# FRONT-UNIT.net
KiCad netlist of a schematic drawn in Altium Designer
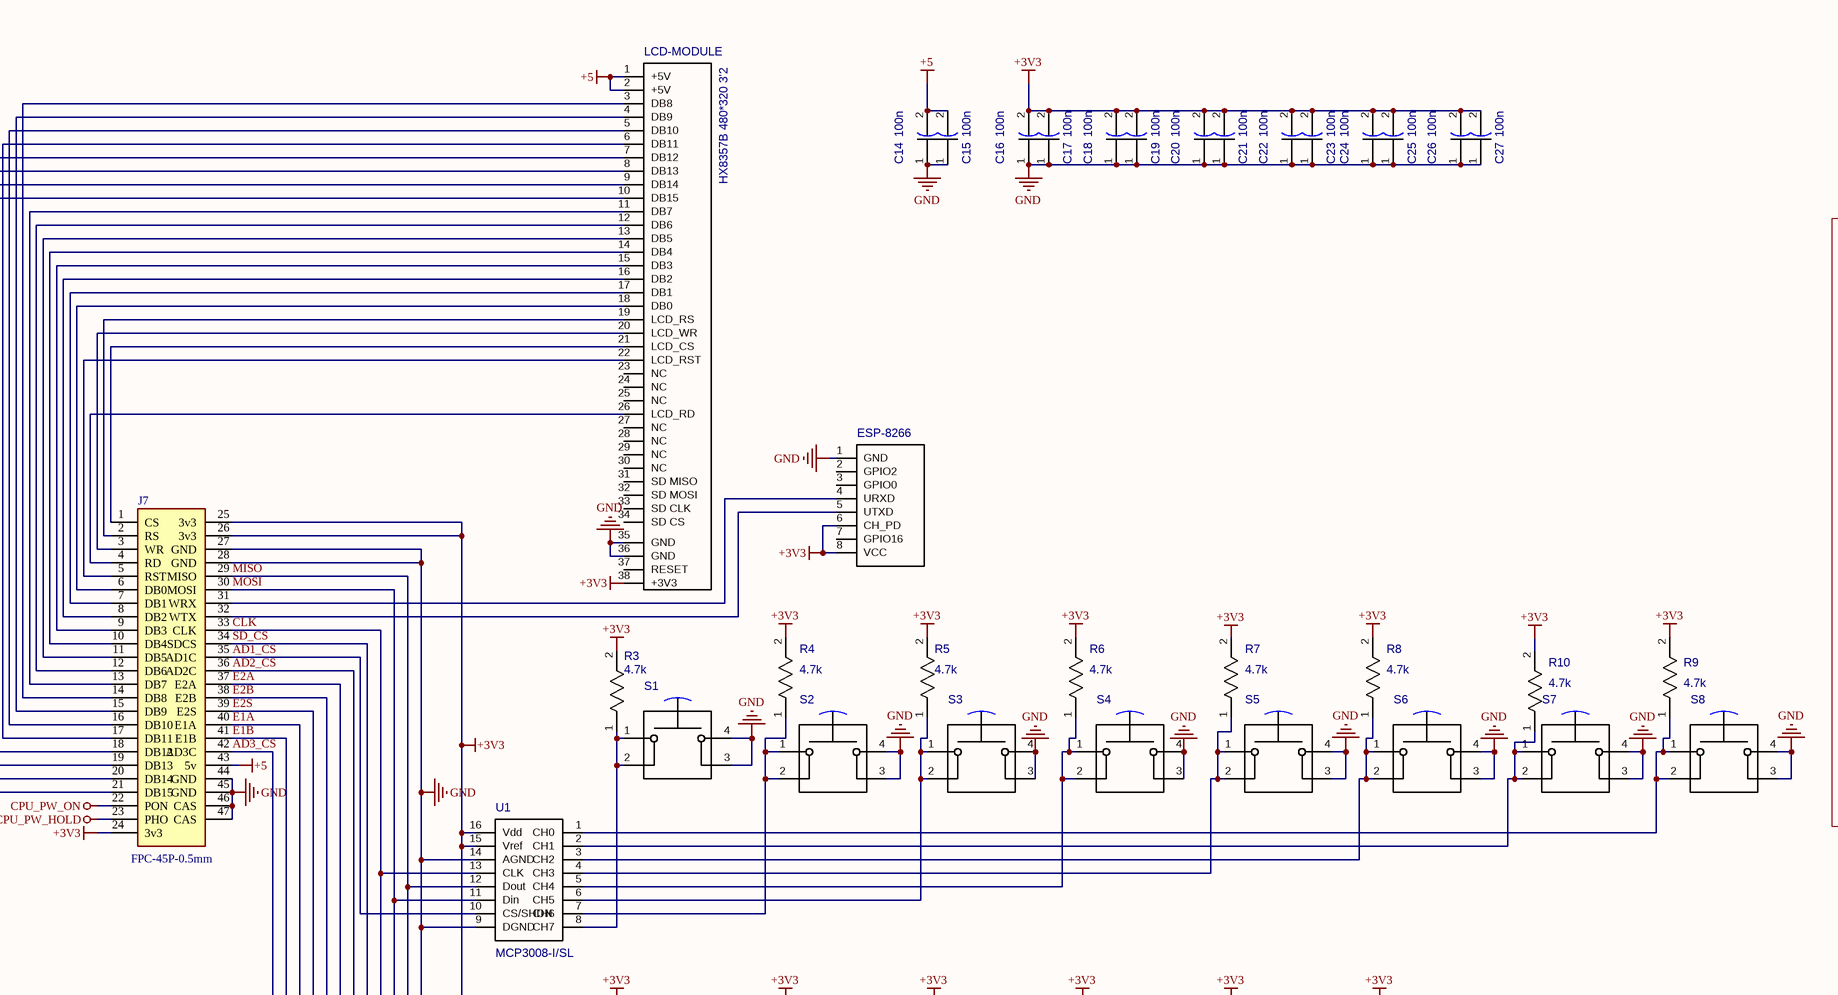
[diagram p0: FRONT-UNIT.SchDoc, top left]
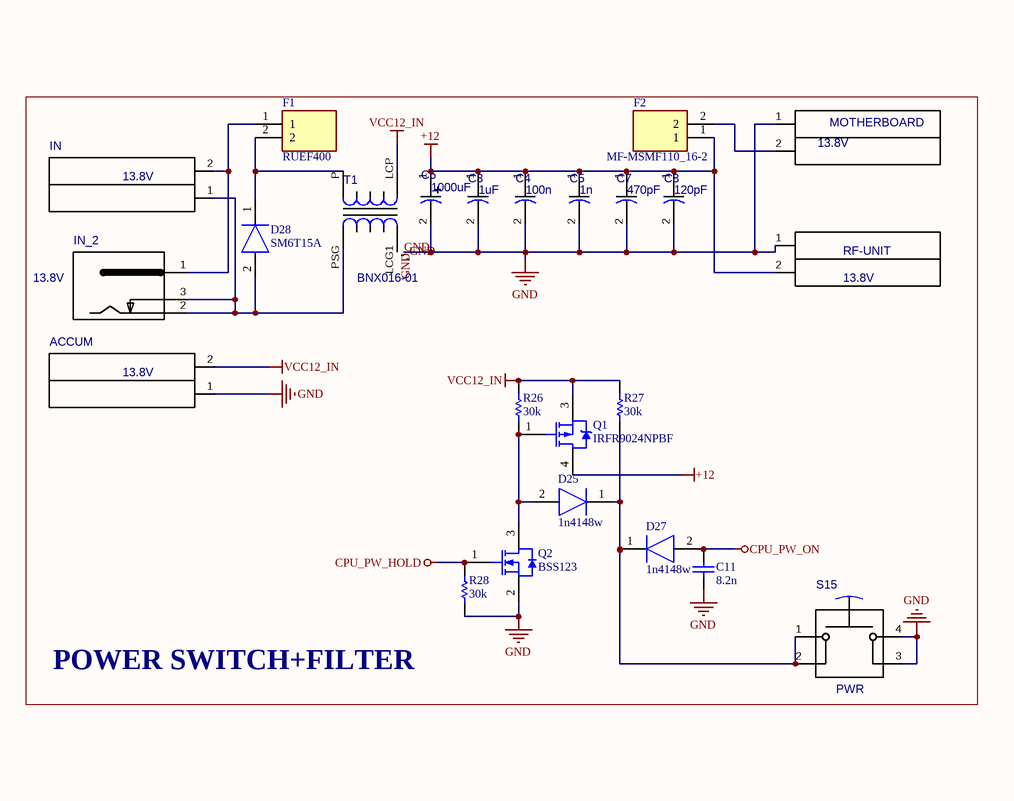
[diagram p1: FRONT-UNIT.SchDoc, top right]
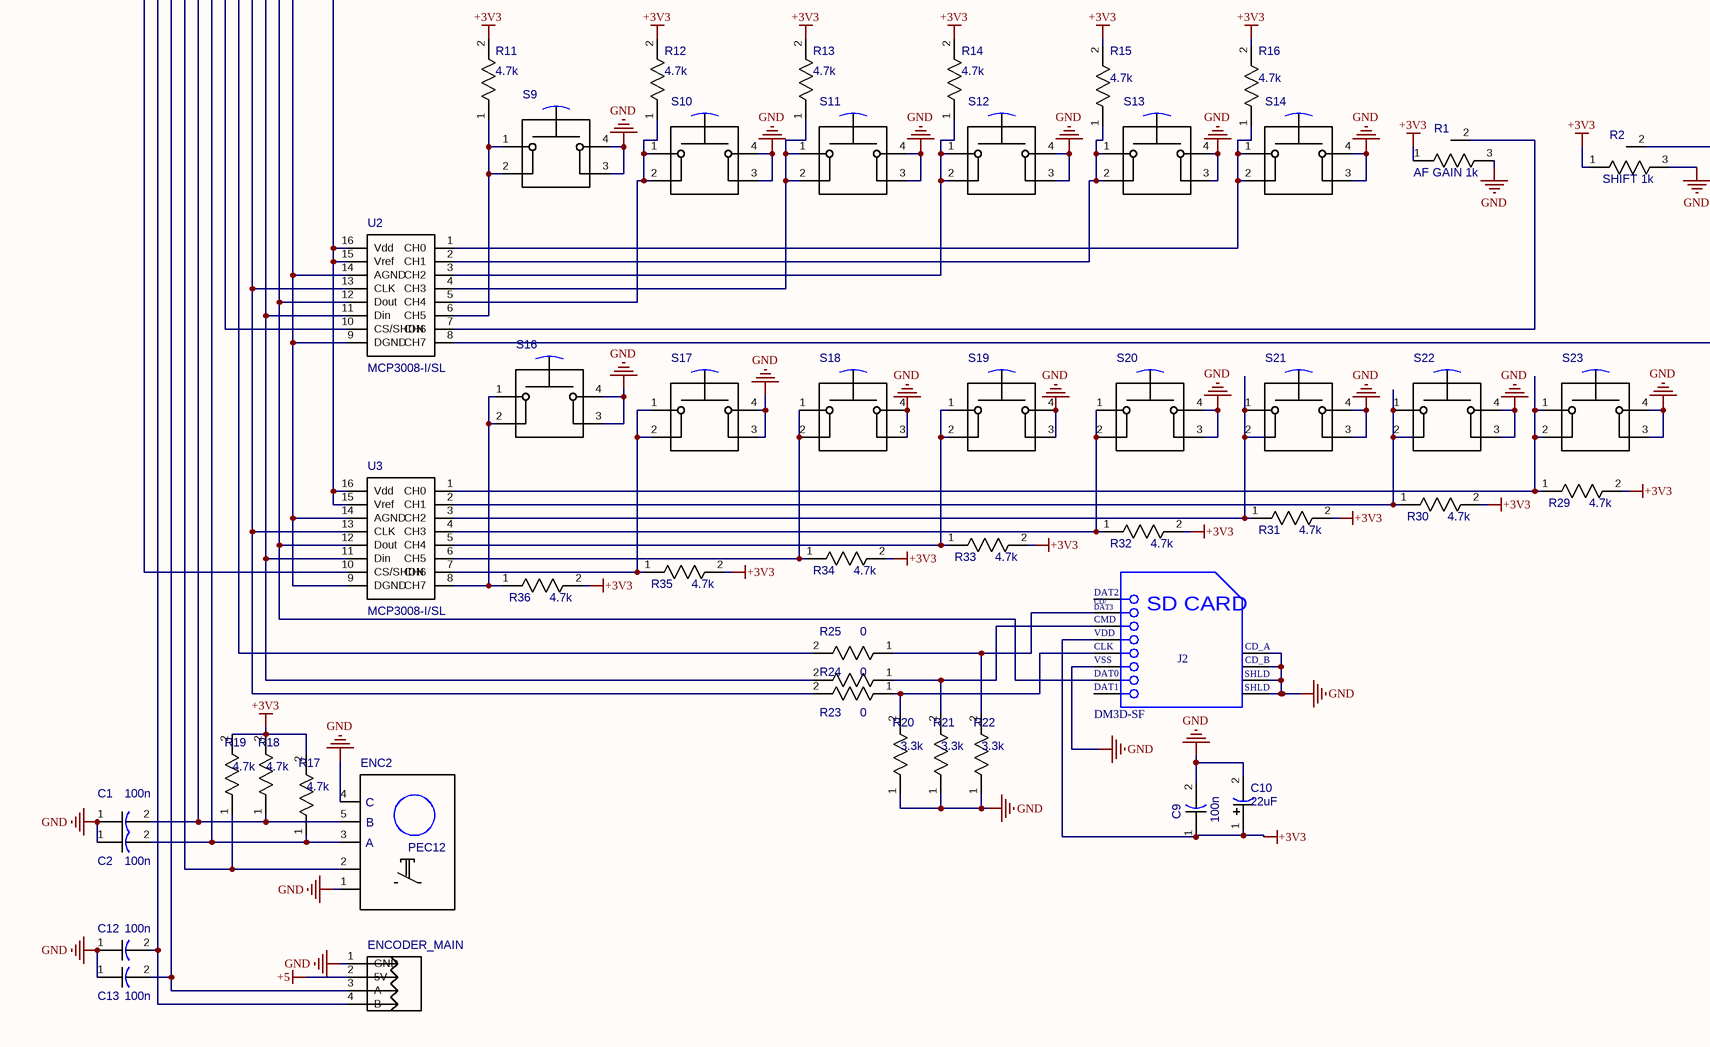
[diagram p2: FRONT-UNIT.SchDoc, bottom left]
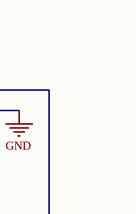
[diagram p3: FRONT-UNIT.SchDoc, bottom right]

(export (version "E")
  (design (tool "Eeschema 10.0.6"))
  (components
    (comp (ref "ACCUM")
      (value "13.8V")
      (footprint "JX2")
      (description "JX2")
      (libsource (lib "*") (part "JX2"))
    )
    (comp (ref "C1")
      (value "100n")
      (footprint "CAP_0805")
      (description "CAP_0805")
      (libsource (lib "*") (part "CAP_0805"))
    )
    (comp (ref "C2")
      (value "100n")
      (footprint "CAP_0805")
      (description "CAP_0805")
      (libsource (lib "*") (part "CAP_0805"))
    )
    (comp (ref "C3")
      (value "1uF")
      (footprint "CAP_1206")
      (description "CAP_1206")
      (libsource (lib "*") (part "CAP_1206"))
    )
    (comp (ref "C4")
      (value "100n")
      (footprint "CAP_1206")
      (description "CAP_1206")
      (libsource (lib "*") (part "CAP_1206"))
    )
    (comp (ref "C5")
      (value "1n")
      (footprint "CAP_1206")
      (description "CAP_1206")
      (libsource (lib "*") (part "CAP_1206"))
    )
    (comp (ref "C6")
      (value "1000uF")
      (footprint "CAP250RP")
      (description "CAP250RP")
      (libsource (lib "*") (part "CAP250RP"))
    )
    (comp (ref "C7")
      (value "470pF")
      (footprint "CAP_1206")
      (description "CAP_1206")
      (libsource (lib "*") (part "CAP_1206"))
    )
    (comp (ref "C8")
      (value "120pF")
      (footprint "CAP_1206")
      (description "CAP_1206")
      (libsource (lib "*") (part "CAP_1206"))
    )
    (comp (ref "C9")
      (value "100n")
      (footprint "CAP_0805")
      (description "CAP_0805")
      (libsource (lib "*") (part "CAP_0805"))
    )
    (comp (ref "C10")
      (value "22uF")
      (footprint "EEEFC_sizeB")
      (description "EEEFC_sizeB")
      (libsource (lib "*") (part "EEEFC_sizeB"))
    )
    (comp (ref "C11")
      (value "8.2n")
      (footprint "CAPC2013X94X50LL20T25")
      (description "CAP_1206")
      (fields
        (field (name "MANUFACTURER") "AVX Interconnect / Elco")
        (field (name "PART NUMBER") "08055C822KAT2A")
      )
      (libsource (lib "Altium Content Vault") (part "CAP"))
    )
    (comp (ref "C12")
      (value "100n")
      (footprint "CAP_0805")
      (description "CAP_0805")
      (libsource (lib "*") (part "CAP_0805"))
    )
    (comp (ref "C13")
      (value "100n")
      (footprint "CAP_0805")
      (description "CAP_0805")
      (libsource (lib "*") (part "CAP_0805"))
    )
    (comp (ref "C14")
      (value "100n")
      (footprint "CAP_0805")
      (description "CAP_0805")
      (libsource (lib "*") (part "CAP_0805"))
    )
    (comp (ref "C15")
      (value "100n")
      (footprint "CAP_0805")
      (description "CAP_0805")
      (libsource (lib "*") (part "CAP_0805"))
    )
    (comp (ref "C16")
      (value "100n")
      (footprint "CAP_0805")
      (description "CAP_0805")
      (libsource (lib "*") (part "CAP_0805"))
    )
    (comp (ref "C17")
      (value "100n")
      (footprint "CAP_0805")
      (description "CAP_0805")
      (libsource (lib "*") (part "CAP_0805"))
    )
    (comp (ref "C18")
      (value "100n")
      (footprint "CAP_0805")
      (description "CAP_0805")
      (libsource (lib "*") (part "CAP_0805"))
    )
    (comp (ref "C19")
      (value "100n")
      (footprint "CAP_0805")
      (description "CAP_0805")
      (libsource (lib "*") (part "CAP_0805"))
    )
    (comp (ref "C20")
      (value "100n")
      (footprint "CAP_0805")
      (description "CAP_0805")
      (libsource (lib "*") (part "CAP_0805"))
    )
    (comp (ref "C21")
      (value "100n")
      (footprint "CAP_0805")
      (description "CAP_0805")
      (libsource (lib "*") (part "CAP_0805"))
    )
    (comp (ref "C22")
      (value "100n")
      (footprint "CAP_0805")
      (description "CAP_0805")
      (libsource (lib "*") (part "CAP_0805"))
    )
    (comp (ref "C23")
      (value "100n")
      (footprint "CAP_0805")
      (description "CAP_0805")
      (libsource (lib "*") (part "CAP_0805"))
    )
    (comp (ref "C24")
      (value "100n")
      (footprint "CAP_0805")
      (description "CAP_0805")
      (libsource (lib "*") (part "CAP_0805"))
    )
    (comp (ref "C25")
      (value "100n")
      (footprint "CAP_0805")
      (description "CAP_0805")
      (libsource (lib "*") (part "CAP_0805"))
    )
    (comp (ref "C26")
      (value "100n")
      (footprint "CAP_0805")
      (description "CAP_0805")
      (libsource (lib "*") (part "CAP_0805"))
    )
    (comp (ref "C27")
      (value "100n")
      (footprint "CAP_0805")
      (description "CAP_0805")
      (libsource (lib "*") (part "CAP_0805"))
    )
    (comp (ref "D25")
      (value "1n4148w")
      (footprint "SamacSys:SOD3716X135N")
      (description "Diode")
      (libsource (lib "*") (part "1n4148w"))
    )
    (comp (ref "D27")
      (value "1n4148w")
      (footprint "SamacSys:SOD3716X135N")
      (description "Diode")
      (libsource (lib "*") (part "1n4148w"))
    )
    (comp (ref "D28")
      (value "SM6T15A")
      (footprint "SamacSys:SMBJ36CATR")
      (description "Diode")
      (fields (field (name "MOUSER PART NUMBER") "511-SM6T15A") (field (name "RS PART NUMBER") "4864915P"))
      (libsource (lib "*") (part "SM6T15A"))
    )
    (comp (ref "ENC2") (value "PEC12") (footprint "PEC12") (libsource (lib "*") (part "PEC12")))
    (comp (ref "ENCODER_MAIN")
      (value "OPTICAL ENCODER")
      (footprint "644456-4")
      (libsource (lib "*") (part "644456-4"))
    )
    (comp (ref "ESP-8266")
      (value "ESP-01 ESP8266")
      (footprint "ESP-01 ESP8266")
      (libsource (lib "*") (part "ESP-01 ESP8266"))
    )
    (comp (ref "F1")
      (value "RUEF400")
      (footprint "SamacSys:RUEF400")
      (description "Fuse")
      (fields (field (name "MOUSER PART NUMBER") "650-RUEF400") (field (name "RS PART NUMBER") "5176837P"))
      (libsource (lib "*") (part "RUEF400"))
    )
    (comp (ref "F2")
      (value "MF-MSMF110_16-2")
      (footprint "SamacSys:FUSC4632X85N")
      (description "Fuse")
      (fields
        (field (name "MANUFACTURER_PART_NUMBER") "MF-MSMF110/16-2")
        (field (name "MOUSER PART NUMBER") "652-MF-MSMF110/16-2")
      )
      (libsource (lib "*") (part "MF-MSMF110_16-2"))
    )
    (comp (ref "IN") (value "13.8V") (footprint "JX2") (description "JX2") (libsource (lib "*") (part "JX2")))
    (comp (ref "IN_2")
      (value "13.8V")
      (footprint "PJ-050B")
      (description "PJ-050B")
      (libsource (lib "*") (part "PJ-050B"))
    )
    (comp (ref "J2")
      (value "DM3D-SF")
      (footprint "HIRO-DM3D-SF_V")
      (fields (field (name "MANUFACTURER") "Hirose Electric"))
      (libsource (lib "Altium Content Vault") (part "CN-SD-8-2SW-2S"))
    )
    (comp (ref "J7")
      (value "FPC-45P-0.5mm")
      (footprint "SamacSys:FH12S45S05SH60")
      (description "Connector")
      (fields
        (field (name "MANUFACTURER_PART_NUMBER") "FH12S-45S-0.5SH(55)")
        (field (name "MOUSER PART NUMBER") "798-FH12S-45S-05SH55")
      )
      (libsource (lib "*") (part "FH12S-45S-0.5SH_55_"))
    )
    (comp (ref "LCD-MODULE")
      (value "HX8357B 480*320 3'2")
      (footprint "LCD-MODULE-3.2-480-320")
      (description "LCD-MODULE_3'2_480х320")
      (libsource (lib "FRONT-UNIT") (part "LCD-MODULE_3'2_480х320"))
    )
    (comp (ref "MOTHERBOARD")
      (value "13.8V")
      (footprint "JX2")
      (description "JX2")
      (libsource (lib "*") (part "JX2"))
    )
    (comp (ref "Q1")
      (value "IRFR9024NPBF")
      (footprint "ONSC-DPAK-3-369C-01_V")
      (description "IRFR9024NPBF, Транзистор, Р-канал 55В 11А")
      (fields (field (name "MANUFACTURER") "On Semiconductor") (field (name "PARTNUMBER") "NTD2955G"))
      (libsource (lib "Altium Content Vault") (part "ONSC-PMOS-G1S3D4-3_B"))
    )
    (comp (ref "Q2")
      (value "BSS123")
      (footprint "FAIR-SOT23-3_V")
      (fields (field (name "MANUFACTURER") "Fairchild"))
      (libsource (lib "Altium Content Vault") (part "NEMOS-GSD-3"))
    )
    (comp (ref "R1")
      (value "AF GAIN 1k")
      (footprint "PTV09")
      (description "Adjustable Resistor PTV09")
      (fields (field (name "Comment") "ptv09a-4225f-b102"))
      (libsource (lib "*") (part "PTV09"))
    )
    (comp (ref "R2")
      (value "SHIFT 1k")
      (footprint "PTV09")
      (description "Adjustable Resistor PTV09")
      (fields (field (name "Comment") "ptv09a-4225f-b102"))
      (libsource (lib "*") (part "PTV09"))
    )
    (comp (ref "R3")
      (value "4.7k")
      (footprint "RES_0805")
      (description "RES_0805")
      (libsource (lib "*") (part "RES_0805"))
    )
    (comp (ref "R4")
      (value "4.7k")
      (footprint "RES_0805")
      (description "RES_0805")
      (libsource (lib "*") (part "RES_0805"))
    )
    (comp (ref "R5")
      (value "4.7k")
      (footprint "RES_0805")
      (description "RES_0805")
      (libsource (lib "*") (part "RES_0805"))
    )
    (comp (ref "R6")
      (value "4.7k")
      (footprint "RES_0805")
      (description "RES_0805")
      (libsource (lib "*") (part "RES_0805"))
    )
    (comp (ref "R7")
      (value "4.7k")
      (footprint "RES_0805")
      (description "RES_0805")
      (libsource (lib "*") (part "RES_0805"))
    )
    (comp (ref "R8")
      (value "4.7k")
      (footprint "RES_0805")
      (description "RES_0805")
      (libsource (lib "*") (part "RES_0805"))
    )
    (comp (ref "R9")
      (value "4.7k")
      (footprint "RES_0805")
      (description "RES_0805")
      (libsource (lib "*") (part "RES_0805"))
    )
    (comp (ref "R10")
      (value "4.7k")
      (footprint "RES_0805")
      (description "RES_0805")
      (libsource (lib "*") (part "RES_0805"))
    )
    (comp (ref "R11")
      (value "4.7k")
      (footprint "RES_0805")
      (description "RES_0805")
      (libsource (lib "*") (part "RES_0805"))
    )
    (comp (ref "R12")
      (value "4.7k")
      (footprint "RES_0805")
      (description "RES_0805")
      (libsource (lib "*") (part "RES_0805"))
    )
    (comp (ref "R13")
      (value "4.7k")
      (footprint "RES_0805")
      (description "RES_0805")
      (libsource (lib "*") (part "RES_0805"))
    )
    (comp (ref "R14")
      (value "4.7k")
      (footprint "RES_0805")
      (description "RES_0805")
      (libsource (lib "*") (part "RES_0805"))
    )
    (comp (ref "R15")
      (value "4.7k")
      (footprint "RES_0805")
      (description "RES_0805")
      (libsource (lib "*") (part "RES_0805"))
    )
    (comp (ref "R16")
      (value "4.7k")
      (footprint "RES_0805")
      (description "RES_0805")
      (libsource (lib "*") (part "RES_0805"))
    )
    (comp (ref "R17")
      (value "4.7k")
      (footprint "RES_0805")
      (description "RES_0805")
      (libsource (lib "*") (part "RES_0805"))
    )
    (comp (ref "R18")
      (value "4.7k")
      (footprint "RES_0805")
      (description "RES_0805")
      (libsource (lib "*") (part "RES_0805"))
    )
    (comp (ref "R19")
      (value "4.7k")
      (footprint "RES_0805")
      (description "RES_0805")
      (libsource (lib "*") (part "RES_0805"))
    )
    (comp (ref "R20")
      (value "3.3k")
      (footprint "RES_0805")
      (description "RES_0805")
      (libsource (lib "*") (part "RES_0805"))
    )
    (comp (ref "R21")
      (value "3.3k")
      (footprint "RES_0805")
      (description "RES_0805")
      (libsource (lib "*") (part "RES_0805"))
    )
    (comp (ref "R22")
      (value "3.3k")
      (footprint "RES_0805")
      (description "RES_0805")
      (libsource (lib "*") (part "RES_0805"))
    )
    (comp (ref "R23")
      (value "0")
      (footprint "RES_0805")
      (description "RES_0805")
      (libsource (lib "*") (part "RES_0805"))
    )
    (comp (ref "R24")
      (value "0")
      (footprint "RES_0805")
      (description "RES_0805")
      (libsource (lib "*") (part "RES_0805"))
    )
    (comp (ref "R25")
      (value "0")
      (footprint "RES_0805")
      (description "RES_0805")
      (libsource (lib "*") (part "RES_0805"))
    )
    (comp (ref "R26")
      (value "30k")
      (footprint "RESC2013X60X40NL20T25")
      (description "RES_0805")
      (fields (field (name "MANUFACTURER") "Panasonic") (field (name "PART NUMBER") "ERA-6AEB303V"))
      (libsource (lib "Altium Content Vault") (part "RES"))
    )
    (comp (ref "R27")
      (value "30k")
      (footprint "RESC2013X60X40NL20T25")
      (description "RES_0805")
      (fields (field (name "MANUFACTURER") "Panasonic") (field (name "PART NUMBER") "ERA-6AEB303V"))
      (libsource (lib "Altium Content Vault") (part "RES"))
    )
    (comp (ref "R28")
      (value "30k")
      (footprint "RESC2013X60X40NL20T25")
      (description "RES_0805")
      (fields (field (name "MANUFACTURER") "Panasonic") (field (name "PART NUMBER") "ERA-6AEB303V"))
      (libsource (lib "Altium Content Vault") (part "RES"))
    )
    (comp (ref "R29")
      (value "4.7k")
      (footprint "RES_0805")
      (description "RES_0805")
      (libsource (lib "*") (part "RES_0805"))
    )
    (comp (ref "R30")
      (value "4.7k")
      (footprint "RES_0805")
      (description "RES_0805")
      (libsource (lib "*") (part "RES_0805"))
    )
    (comp (ref "R31")
      (value "4.7k")
      (footprint "RES_0805")
      (description "RES_0805")
      (libsource (lib "*") (part "RES_0805"))
    )
    (comp (ref "R32")
      (value "4.7k")
      (footprint "RES_0805")
      (description "RES_0805")
      (libsource (lib "*") (part "RES_0805"))
    )
    (comp (ref "R33")
      (value "4.7k")
      (footprint "RES_0805")
      (description "RES_0805")
      (libsource (lib "*") (part "RES_0805"))
    )
    (comp (ref "R34")
      (value "4.7k")
      (footprint "RES_0805")
      (description "RES_0805")
      (libsource (lib "*") (part "RES_0805"))
    )
    (comp (ref "R35")
      (value "4.7k")
      (footprint "RES_0805")
      (description "RES_0805")
      (libsource (lib "*") (part "RES_0805"))
    )
    (comp (ref "R36")
      (value "4.7k")
      (footprint "RES_0805")
      (description "RES_0805")
      (libsource (lib "*") (part "RES_0805"))
    )
    (comp (ref "RF-UNIT")
      (value "13.8V")
      (footprint "JX2")
      (description "JX2")
      (libsource (lib "*") (part "JX2"))
    )
    (comp (ref "S1")
      (value "PTS645SK50LFS")
      (footprint "PTS645SK50LFS")
      (libsource (lib "*") (part "PTS645SK50LFS"))
    )
    (comp (ref "S2")
      (value "PTS645SK50LFS")
      (footprint "PTS645SK50LFS")
      (libsource (lib "*") (part "PTS645SK50LFS"))
    )
    (comp (ref "S3")
      (value "PTS645SK50LFS")
      (footprint "PTS645SK50LFS")
      (libsource (lib "*") (part "PTS645SK50LFS"))
    )
    (comp (ref "S4")
      (value "PTS645SK50LFS")
      (footprint "PTS645SK50LFS")
      (libsource (lib "*") (part "PTS645SK50LFS"))
    )
    (comp (ref "S5")
      (value "PTS645SK50LFS")
      (footprint "PTS645SK50LFS")
      (libsource (lib "*") (part "PTS645SK50LFS"))
    )
    (comp (ref "S6")
      (value "PTS645SK50LFS")
      (footprint "PTS645SK50LFS")
      (libsource (lib "*") (part "PTS645SK50LFS"))
    )
    (comp (ref "S7")
      (value "PTS645SK50LFS")
      (footprint "PTS645SK50LFS")
      (libsource (lib "*") (part "PTS645SK50LFS"))
    )
    (comp (ref "S8")
      (value "PTS645SK50LFS")
      (footprint "PTS645SK50LFS")
      (libsource (lib "*") (part "PTS645SK50LFS"))
    )
    (comp (ref "S9")
      (value "PTS645SK50LFS")
      (footprint "PTS645SK50LFS")
      (libsource (lib "*") (part "PTS645SK50LFS"))
    )
    (comp (ref "S10")
      (value "PTS645SK50LFS")
      (footprint "PTS645SK50LFS")
      (libsource (lib "*") (part "PTS645SK50LFS"))
    )
    (comp (ref "S11")
      (value "PTS645SK50LFS")
      (footprint "PTS645SK50LFS")
      (libsource (lib "*") (part "PTS645SK50LFS"))
    )
    (comp (ref "S12")
      (value "PTS645SK50LFS")
      (footprint "PTS645SK50LFS")
      (libsource (lib "*") (part "PTS645SK50LFS"))
    )
    (comp (ref "S13")
      (value "PTS645SK50LFS")
      (footprint "PTS645SK50LFS")
      (libsource (lib "*") (part "PTS645SK50LFS"))
    )
    (comp (ref "S14")
      (value "PTS645SK50LFS")
      (footprint "PTS645SK50LFS")
      (libsource (lib "*") (part "PTS645SK50LFS"))
    )
    (comp (ref "S15")
      (value "PWR")
      (footprint "PTS645SK50LFS")
      (description "PTS645SK50LFS")
      (libsource (lib "*") (part "PTS645SK50LFS"))
    )
    (comp (ref "S16")
      (value "PTS645SK50LFS")
      (footprint "PTS645SK50LFS")
      (libsource (lib "*") (part "PTS645SK50LFS"))
    )
    (comp (ref "S17")
      (value "PTS645SK50LFS")
      (footprint "PTS645SK50LFS")
      (libsource (lib "*") (part "PTS645SK50LFS"))
    )
    (comp (ref "S18")
      (value "PTS645SK50LFS")
      (footprint "PTS645SK50LFS")
      (libsource (lib "*") (part "PTS645SK50LFS"))
    )
    (comp (ref "S19")
      (value "PTS645SK50LFS")
      (footprint "PTS645SK50LFS")
      (libsource (lib "*") (part "PTS645SK50LFS"))
    )
    (comp (ref "S20")
      (value "PTS645SK50LFS")
      (footprint "PTS645SK50LFS")
      (libsource (lib "*") (part "PTS645SK50LFS"))
    )
    (comp (ref "S21")
      (value "PTS645SK50LFS")
      (footprint "PTS645SK50LFS")
      (libsource (lib "*") (part "PTS645SK50LFS"))
    )
    (comp (ref "S22")
      (value "PTS645SK50LFS")
      (footprint "PTS645SK50LFS")
      (libsource (lib "*") (part "PTS645SK50LFS"))
    )
    (comp (ref "S23")
      (value "PTS645SK50LFS")
      (footprint "PTS645SK50LFS")
      (libsource (lib "*") (part "PTS645SK50LFS"))
    )
    (comp (ref "T1")
      (value "BNX016-01")
      (footprint "TRANSF_ICORE")
      (libsource (lib "*") (part "TRANSF_ICORE"))
    )
    (comp (ref "U1")
      (value "MCP3008-I/SL")
      (footprint "MCP3008-I/SL")
      (libsource (lib "*") (part "MCP3008-I/SL"))
    )
    (comp (ref "U2")
      (value "MCP3008-I/SL")
      (footprint "MCP3008-I/SL")
      (libsource (lib "*") (part "MCP3008-I/SL"))
    )
    (comp (ref "U3")
      (value "MCP3008-I/SL")
      (footprint "MCP3008-I/SL")
      (libsource (lib "*") (part "MCP3008-I/SL"))
    )
  )
  (nets
    (net (code "1") (name "+3V3") (class "Default")
      (node (ref "C10") (pin "1") (pinfunction "PLUS_1") (pintype "passive"))
      (node (ref "C16") (pin "2") (pinfunction "2_2") (pintype "passive"))
      (node (ref "C17") (pin "2") (pinfunction "2_2") (pintype "passive"))
      (node (ref "C18") (pin "2") (pinfunction "2_2") (pintype "passive"))
      (node (ref "C19") (pin "2") (pinfunction "2_2") (pintype "passive"))
      (node (ref "C20") (pin "2") (pinfunction "2_2") (pintype "passive"))
      (node (ref "C21") (pin "2") (pinfunction "2_2") (pintype "passive"))
      (node (ref "C22") (pin "2") (pinfunction "2_2") (pintype "passive"))
      (node (ref "C23") (pin "2") (pinfunction "2_2") (pintype "passive"))
      (node (ref "C24") (pin "2") (pinfunction "2_2") (pintype "passive"))
      (node (ref "C25") (pin "2") (pinfunction "2_2") (pintype "passive"))
      (node (ref "C26") (pin "2") (pinfunction "2_2") (pintype "passive"))
      (node (ref "C27") (pin "2") (pinfunction "2_2") (pintype "passive"))
      (node (ref "C9") (pin "1") (pinfunction "1_1") (pintype "passive"))
      (node (ref "ESP-8266") (pin "6") (pinfunction "CH_PD_6") (pintype "passive"))
      (node (ref "ESP-8266") (pin "8") (pinfunction "VCC_8") (pintype "passive"))
      (node (ref "J2") (pin "4") (pinfunction "VDD_4") (pintype "passive"))
      (node (ref "J7") (pin "24") (pinfunction "3v3_24") (pintype "passive"))
      (node (ref "J7") (pin "25") (pinfunction "3v3_25") (pintype "passive"))
      (node (ref "J7") (pin "26") (pinfunction "3v3_26") (pintype "passive"))
      (node (ref "LCD-MODULE") (pin "38") (pinfunction "+3V3_38") (pintype "passive"))
      (node (ref "R1") (pin "1") (pinfunction "CW_1") (pintype "passive"))
      (node (ref "R10") (pin "2") (pinfunction "2_2") (pintype "passive"))
      (node (ref "R11") (pin "2") (pinfunction "2_2") (pintype "passive"))
      (node (ref "R12") (pin "2") (pinfunction "2_2") (pintype "passive"))
      (node (ref "R13") (pin "2") (pinfunction "2_2") (pintype "passive"))
      (node (ref "R14") (pin "2") (pinfunction "2_2") (pintype "passive"))
      (node (ref "R15") (pin "2") (pinfunction "2_2") (pintype "passive"))
      (node (ref "R16") (pin "2") (pinfunction "2_2") (pintype "passive"))
      (node (ref "R17") (pin "2") (pinfunction "2_2") (pintype "passive"))
      (node (ref "R18") (pin "2") (pinfunction "2_2") (pintype "passive"))
      (node (ref "R19") (pin "2") (pinfunction "2_2") (pintype "passive"))
      (node (ref "R2") (pin "1") (pinfunction "CW_1") (pintype "passive"))
      (node (ref "R29") (pin "2") (pinfunction "2_2") (pintype "passive"))
      (node (ref "R3") (pin "2") (pinfunction "2_2") (pintype "passive"))
      (node (ref "R30") (pin "2") (pinfunction "2_2") (pintype "passive"))
      (node (ref "R31") (pin "2") (pinfunction "2_2") (pintype "passive"))
      (node (ref "R32") (pin "2") (pinfunction "2_2") (pintype "passive"))
      (node (ref "R33") (pin "2") (pinfunction "2_2") (pintype "passive"))
      (node (ref "R34") (pin "2") (pinfunction "2_2") (pintype "passive"))
      (node (ref "R35") (pin "2") (pinfunction "2_2") (pintype "passive"))
      (node (ref "R36") (pin "2") (pinfunction "2_2") (pintype "passive"))
      (node (ref "R4") (pin "2") (pinfunction "2_2") (pintype "passive"))
      (node (ref "R5") (pin "2") (pinfunction "2_2") (pintype "passive"))
      (node (ref "R6") (pin "2") (pinfunction "2_2") (pintype "passive"))
      (node (ref "R7") (pin "2") (pinfunction "2_2") (pintype "passive"))
      (node (ref "R8") (pin "2") (pinfunction "2_2") (pintype "passive"))
      (node (ref "R9") (pin "2") (pinfunction "2_2") (pintype "passive"))
      (node (ref "U1") (pin "15") (pinfunction "Vref_15") (pintype "passive"))
      (node (ref "U1") (pin "16") (pinfunction "Vdd_16") (pintype "passive"))
      (node (ref "U2") (pin "15") (pinfunction "Vref_15") (pintype "passive"))
      (node (ref "U2") (pin "16") (pinfunction "Vdd_16") (pintype "passive"))
      (node (ref "U3") (pin "15") (pinfunction "Vref_15") (pintype "passive"))
      (node (ref "U3") (pin "16") (pinfunction "Vdd_16") (pintype "passive"))
    )
    (net (code "2") (name "+5") (class "Default")
      (node (ref "C14") (pin "2") (pinfunction "2_2") (pintype "passive"))
      (node (ref "C15") (pin "2") (pinfunction "2_2") (pintype "passive"))
      (node (ref "ENCODER_MAIN") (pin "2") (pinfunction "5V_2") (pintype "passive"))
      (node (ref "J7") (pin "43") (pinfunction "5v_43") (pintype "passive"))
      (node (ref "LCD-MODULE") (pin "1") (pinfunction "+5V_1") (pintype "passive"))
      (node (ref "LCD-MODULE") (pin "2") (pinfunction "+5V_2") (pintype "passive"))
    )
    (net (code "3") (name "+12") (class "Default")
      (node (ref "C3") (pin "1") (pinfunction "1_1") (pintype "passive"))
      (node (ref "C4") (pin "1") (pinfunction "1_1") (pintype "passive"))
      (node (ref "C5") (pin "1") (pinfunction "1_1") (pintype "passive"))
      (node (ref "C6") (pin "1") (pinfunction "PLUS_1") (pintype "passive"))
      (node (ref "C7") (pin "1") (pinfunction "1_1") (pintype "passive"))
      (node (ref "C8") (pin "1") (pinfunction "1_1") (pintype "passive"))
      (node (ref "F2") (pin "1") (pinfunction "1_1") (pintype "passive"))
      (node (ref "Q1") (pin "4") (pinfunction "D_4") (pintype "passive"))
      (node (ref "RF-UNIT") (pin "2") (pinfunction "1_2") (pintype "passive"))
    )
    (net (code "4") (name "/AD1_CS") (class "Default")
      (node (ref "J7") (pin "35") (pinfunction "AD1C_35") (pintype "passive"))
      (node (ref "U1") (pin "10") (pinfunction "CS/SHDN_10") (pintype "passive"))
    )
    (net (code "5") (name "/AD2_CS") (class "Default")
      (node (ref "J7") (pin "36") (pinfunction "AD2C_36") (pintype "passive"))
      (node (ref "U2") (pin "10") (pinfunction "CS/SHDN_10") (pintype "passive"))
    )
    (net (code "6") (name "/AD3_CS") (class "Default")
      (node (ref "J7") (pin "42") (pinfunction "AD3C_42") (pintype "passive"))
      (node (ref "U3") (pin "10") (pinfunction "CS/SHDN_10") (pintype "passive"))
    )
    (net (code "7") (name "/CLK") (class "Default")
      (node (ref "J7") (pin "33") (pinfunction "CLK_33") (pintype "passive"))
      (node (ref "R23") (pin "2") (pinfunction "2_2") (pintype "passive"))
      (node (ref "U1") (pin "13") (pinfunction "CLK_13") (pintype "passive"))
      (node (ref "U2") (pin "13") (pinfunction "CLK_13") (pintype "passive"))
      (node (ref "U3") (pin "13") (pinfunction "CLK_13") (pintype "passive"))
    )
    (net (code "8") (name "/E1A") (class "Default")
      (node (ref "C13") (pin "2") (pinfunction "2_2") (pintype "passive"))
      (node (ref "ENCODER_MAIN") (pin "3") (pinfunction "A_3") (pintype "passive"))
      (node (ref "J7") (pin "40") (pinfunction "E1A_40") (pintype "passive"))
    )
    (net (code "9") (name "/E1B") (class "Default")
      (node (ref "C12") (pin "2") (pinfunction "2_2") (pintype "passive"))
      (node (ref "ENCODER_MAIN") (pin "4") (pinfunction "B_4") (pintype "passive"))
      (node (ref "J7") (pin "41") (pinfunction "E1B_41") (pintype "passive"))
    )
    (net (code "10") (name "/E2A") (class "Default")
      (node (ref "C2") (pin "2") (pinfunction "2_2") (pintype "passive"))
      (node (ref "ENC2") (pin "3") (pinfunction "A_3") (pintype "passive"))
      (node (ref "J7") (pin "37") (pinfunction "E2A_37") (pintype "passive"))
      (node (ref "R17") (pin "1") (pinfunction "1_1") (pintype "passive"))
    )
    (net (code "11") (name "/E2B") (class "Default")
      (node (ref "C1") (pin "2") (pinfunction "2_2") (pintype "passive"))
      (node (ref "ENC2") (pin "5") (pinfunction "B_5") (pintype "passive"))
      (node (ref "J7") (pin "38") (pinfunction "E2B_38") (pintype "passive"))
      (node (ref "R18") (pin "1") (pinfunction "1_1") (pintype "passive"))
    )
    (net (code "12") (name "/E2S") (class "Default")
      (node (ref "ENC2") (pin "2") (pinfunction "2_2") (pintype "passive"))
      (node (ref "J7") (pin "39") (pinfunction "E2S_39") (pintype "passive"))
      (node (ref "R19") (pin "1") (pinfunction "1_1") (pintype "passive"))
    )
    (net (code "13") (name "/MISO") (class "Default")
      (node (ref "J2") (pin "7") (pinfunction "DAT0_7") (pintype "passive"))
      (node (ref "J7") (pin "29") (pinfunction "MISO_29") (pintype "passive"))
      (node (ref "U1") (pin "12") (pinfunction "Dout_12") (pintype "passive"))
      (node (ref "U2") (pin "12") (pinfunction "Dout_12") (pintype "passive"))
      (node (ref "U3") (pin "12") (pinfunction "Dout_12") (pintype "passive"))
    )
    (net (code "14") (name "/MOSI") (class "Default")
      (node (ref "J7") (pin "30") (pinfunction "MOSI_30") (pintype "passive"))
      (node (ref "R24") (pin "2") (pinfunction "2_2") (pintype "passive"))
      (node (ref "U1") (pin "11") (pinfunction "Din_11") (pintype "passive"))
      (node (ref "U2") (pin "11") (pinfunction "Din_11") (pintype "passive"))
      (node (ref "U3") (pin "11") (pinfunction "Din_11") (pintype "passive"))
    )
    (net (code "15") (name "/SD_CS") (class "Default")
      (node (ref "J7") (pin "34") (pinfunction "SDCS_34") (pintype "passive"))
      (node (ref "R25") (pin "2") (pinfunction "2_2") (pintype "passive"))
    )
    (net (code "16") (name "CPU_PW_HOLD") (class "Default")
      (node (ref "J7") (pin "23") (pinfunction "PHO_23") (pintype "passive"))
      (node (ref "Q2") (pin "1") (pinfunction "G_1") (pintype "passive"))
      (node (ref "R28") (pin "2") (pinfunction "2_2") (pintype "passive"))
    )
    (net (code "17") (name "CPU_PW_ON") (class "Default")
      (node (ref "C11") (pin "2") (pinfunction "2_2") (pintype "passive"))
      (node (ref "D27") (pin "2") (pinfunction "A_2") (pintype "passive"))
      (node (ref "J7") (pin "22") (pinfunction "PON_22") (pintype "passive"))
    )
    (net (code "18") (name "GND") (class "Default")
      (node (ref "ACCUM") (pin "1") (pinfunction "2_1") (pintype "passive"))
      (node (ref "C1") (pin "1") (pinfunction "1_1") (pintype "passive"))
      (node (ref "C10") (pin "2") (pinfunction "MINUS_2") (pintype "passive"))
      (node (ref "C11") (pin "1") (pinfunction "1_1") (pintype "passive"))
      (node (ref "C12") (pin "1") (pinfunction "1_1") (pintype "passive"))
      (node (ref "C13") (pin "1") (pinfunction "1_1") (pintype "passive"))
      (node (ref "C14") (pin "1") (pinfunction "1_1") (pintype "passive"))
      (node (ref "C15") (pin "1") (pinfunction "1_1") (pintype "passive"))
      (node (ref "C16") (pin "1") (pinfunction "1_1") (pintype "passive"))
      (node (ref "C17") (pin "1") (pinfunction "1_1") (pintype "passive"))
      (node (ref "C18") (pin "1") (pinfunction "1_1") (pintype "passive"))
      (node (ref "C19") (pin "1") (pinfunction "1_1") (pintype "passive"))
      (node (ref "C2") (pin "1") (pinfunction "1_1") (pintype "passive"))
      (node (ref "C20") (pin "1") (pinfunction "1_1") (pintype "passive"))
      (node (ref "C21") (pin "1") (pinfunction "1_1") (pintype "passive"))
      (node (ref "C22") (pin "1") (pinfunction "1_1") (pintype "passive"))
      (node (ref "C23") (pin "1") (pinfunction "1_1") (pintype "passive"))
      (node (ref "C24") (pin "1") (pinfunction "1_1") (pintype "passive"))
      (node (ref "C25") (pin "1") (pinfunction "1_1") (pintype "passive"))
      (node (ref "C26") (pin "1") (pinfunction "1_1") (pintype "passive"))
      (node (ref "C27") (pin "1") (pinfunction "1_1") (pintype "passive"))
      (node (ref "C3") (pin "2") (pinfunction "2_2") (pintype "passive"))
      (node (ref "C4") (pin "2") (pinfunction "2_2") (pintype "passive"))
      (node (ref "C5") (pin "2") (pinfunction "2_2") (pintype "passive"))
      (node (ref "C6") (pin "2") (pinfunction "MINUS_2") (pintype "passive"))
      (node (ref "C7") (pin "2") (pinfunction "2_2") (pintype "passive"))
      (node (ref "C8") (pin "2") (pinfunction "2_2") (pintype "passive"))
      (node (ref "C9") (pin "2") (pinfunction "2_2") (pintype "passive"))
      (node (ref "ENC2") (pin "1") (pinfunction "1_1") (pintype "passive"))
      (node (ref "ENC2") (pin "4") (pinfunction "C_4") (pintype "passive"))
      (node (ref "ENCODER_MAIN") (pin "1") (pinfunction "GND_1") (pintype "passive"))
      (node (ref "ESP-8266") (pin "1") (pinfunction "GND_1") (pintype "passive"))
      (node (ref "J2") (pin "10") (pinfunction "CD_B_10") (pintype "passive"))
      (node (ref "J2") (pin "11") (pinfunction "SHLD1_11") (pintype "passive"))
      (node (ref "J2") (pin "12") (pinfunction "SHLD2_12") (pintype "passive"))
      (node (ref "J2") (pin "13") (pinfunction "SHLD3_13") (pintype "passive"))
      (node (ref "J2") (pin "14") (pinfunction "SHLD4_14") (pintype "passive"))
      (node (ref "J2") (pin "6") (pinfunction "VSS2_6") (pintype "passive"))
      (node (ref "J2") (pin "9") (pinfunction "CD_A_9") (pintype "passive"))
      (node (ref "J7") (pin "27") (pinfunction "GND_27") (pintype "passive"))
      (node (ref "J7") (pin "28") (pinfunction "GND_28") (pintype "passive"))
      (node (ref "J7") (pin "44") (pinfunction "GND_44") (pintype "passive"))
      (node (ref "J7") (pin "45") (pinfunction "GND_45") (pintype "passive"))
      (node (ref "J7") (pin "46") (pinfunction "CAS_46") (pintype "passive"))
      (node (ref "J7") (pin "47") (pinfunction "CAS_47") (pintype "passive"))
      (node (ref "LCD-MODULE") (pin "35") (pinfunction "GND_35") (pintype "passive"))
      (node (ref "LCD-MODULE") (pin "36") (pinfunction "GND_36") (pintype "passive"))
      (node (ref "MOTHERBOARD") (pin "1") (pinfunction "2_1") (pintype "passive"))
      (node (ref "Q2") (pin "2") (pinfunction "S_2") (pintype "passive"))
      (node (ref "R1") (pin "3") (pinfunction "CCW_3") (pintype "passive"))
      (node (ref "R2") (pin "3") (pinfunction "CCW_3") (pintype "passive"))
      (node (ref "R20") (pin "1") (pinfunction "1_1") (pintype "passive"))
      (node (ref "R21") (pin "1") (pinfunction "1_1") (pintype "passive"))
      (node (ref "R22") (pin "1") (pinfunction "1_1") (pintype "passive"))
      (node (ref "R28") (pin "1") (pinfunction "1_1") (pintype "passive"))
      (node (ref "RF-UNIT") (pin "1") (pinfunction "2_1") (pintype "passive"))
      (node (ref "S1") (pin "3") (pinfunction "B_3") (pintype "passive"))
      (node (ref "S1") (pin "4") (pinfunction "B_4") (pintype "passive"))
      (node (ref "S10") (pin "3") (pinfunction "B_3") (pintype "passive"))
      (node (ref "S10") (pin "4") (pinfunction "B_4") (pintype "passive"))
      (node (ref "S11") (pin "3") (pinfunction "B_3") (pintype "passive"))
      (node (ref "S11") (pin "4") (pinfunction "B_4") (pintype "passive"))
      (node (ref "S12") (pin "3") (pinfunction "B_3") (pintype "passive"))
      (node (ref "S12") (pin "4") (pinfunction "B_4") (pintype "passive"))
      (node (ref "S13") (pin "3") (pinfunction "B_3") (pintype "passive"))
      (node (ref "S13") (pin "4") (pinfunction "B_4") (pintype "passive"))
      (node (ref "S14") (pin "3") (pinfunction "B_3") (pintype "passive"))
      (node (ref "S14") (pin "4") (pinfunction "B_4") (pintype "passive"))
      (node (ref "S15") (pin "3") (pinfunction "B_3") (pintype "passive"))
      (node (ref "S15") (pin "4") (pinfunction "B_4") (pintype "passive"))
      (node (ref "S16") (pin "3") (pinfunction "B_3") (pintype "passive"))
      (node (ref "S16") (pin "4") (pinfunction "B_4") (pintype "passive"))
      (node (ref "S17") (pin "3") (pinfunction "B_3") (pintype "passive"))
      (node (ref "S17") (pin "4") (pinfunction "B_4") (pintype "passive"))
      (node (ref "S18") (pin "3") (pinfunction "B_3") (pintype "passive"))
      (node (ref "S18") (pin "4") (pinfunction "B_4") (pintype "passive"))
      (node (ref "S19") (pin "3") (pinfunction "B_3") (pintype "passive"))
      (node (ref "S19") (pin "4") (pinfunction "B_4") (pintype "passive"))
      (node (ref "S2") (pin "3") (pinfunction "B_3") (pintype "passive"))
      (node (ref "S2") (pin "4") (pinfunction "B_4") (pintype "passive"))
      (node (ref "S20") (pin "3") (pinfunction "B_3") (pintype "passive"))
      (node (ref "S20") (pin "4") (pinfunction "B_4") (pintype "passive"))
      (node (ref "S21") (pin "3") (pinfunction "B_3") (pintype "passive"))
      (node (ref "S21") (pin "4") (pinfunction "B_4") (pintype "passive"))
      (node (ref "S22") (pin "3") (pinfunction "B_3") (pintype "passive"))
      (node (ref "S22") (pin "4") (pinfunction "B_4") (pintype "passive"))
      (node (ref "S23") (pin "3") (pinfunction "B_3") (pintype "passive"))
      (node (ref "S23") (pin "4") (pinfunction "B_4") (pintype "passive"))
      (node (ref "S3") (pin "3") (pinfunction "B_3") (pintype "passive"))
      (node (ref "S3") (pin "4") (pinfunction "B_4") (pintype "passive"))
      (node (ref "S4") (pin "3") (pinfunction "B_3") (pintype "passive"))
      (node (ref "S4") (pin "4") (pinfunction "B_4") (pintype "passive"))
      (node (ref "S5") (pin "3") (pinfunction "B_3") (pintype "passive"))
      (node (ref "S5") (pin "4") (pinfunction "B_4") (pintype "passive"))
      (node (ref "S6") (pin "3") (pinfunction "B_3") (pintype "passive"))
      (node (ref "S6") (pin "4") (pinfunction "B_4") (pintype "passive"))
      (node (ref "S7") (pin "3") (pinfunction "B_3") (pintype "passive"))
      (node (ref "S7") (pin "4") (pinfunction "B_4") (pintype "passive"))
      (node (ref "S8") (pin "3") (pinfunction "B_3") (pintype "passive"))
      (node (ref "S8") (pin "4") (pinfunction "B_4") (pintype "passive"))
      (node (ref "S9") (pin "3") (pinfunction "B_3") (pintype "passive"))
      (node (ref "S9") (pin "4") (pinfunction "B_4") (pintype "passive"))
      (node (ref "T1") (pin "LCG1") (pinfunction "S2_LCG1") (pintype "passive"))
      (node (ref "T1") (pin "LCG2") (pinfunction "0_LCG2") (pintype "passive"))
      (node (ref "T1") (pin "LCG3") (pinfunction "0_LCG3") (pintype "passive"))
      (node (ref "U1") (pin "14") (pinfunction "AGND_14") (pintype "passive"))
      (node (ref "U1") (pin "9") (pinfunction "DGND_9") (pintype "passive"))
      (node (ref "U2") (pin "14") (pinfunction "AGND_14") (pintype "passive"))
      (node (ref "U2") (pin "9") (pinfunction "DGND_9") (pintype "passive"))
      (node (ref "U3") (pin "14") (pinfunction "AGND_14") (pintype "passive"))
      (node (ref "U3") (pin "9") (pinfunction "DGND_9") (pintype "passive"))
    )
    (net (code "19") (name "Net-(D25-A)") (class "Default")
      (node (ref "D25") (pin "2") (pinfunction "A_2") (pintype "passive"))
      (node (ref "Q1") (pin "1") (pinfunction "G_1") (pintype "passive"))
      (node (ref "Q2") (pin "3") (pinfunction "D_3") (pintype "passive"))
      (node (ref "R26") (pin "1") (pinfunction "1_1") (pintype "passive"))
    )
    (net (code "20") (name "Net-(D25-K)") (class "Default")
      (node (ref "D25") (pin "1") (pinfunction "K_1") (pintype "passive"))
      (node (ref "D27") (pin "1") (pinfunction "K_1") (pintype "passive"))
      (node (ref "R27") (pin "1") (pinfunction "1_1") (pintype "passive"))
      (node (ref "S15") (pin "1") (pinfunction "A_1") (pintype "passive"))
      (node (ref "S15") (pin "2") (pinfunction "A_2") (pintype "passive"))
    )
    (net (code "21") (name "Net-(D28-A)") (class "Default")
      (node (ref "D28") (pin "2") (pinfunction "A_2") (pintype "passive"))
      (node (ref "IN") (pin "1") (pinfunction "2_1") (pintype "passive"))
      (node (ref "IN_2") (pin "2") (pinfunction "2_2") (pintype "passive"))
      (node (ref "IN_2") (pin "3") (pinfunction "3_3") (pintype "passive"))
      (node (ref "T1") (pin "PSG") (pinfunction "S1_PSG") (pintype "passive"))
    )
    (net (code "22") (name "Net-(D28-K)") (class "Default")
      (node (ref "D28") (pin "1") (pinfunction "K_1") (pintype "passive"))
      (node (ref "F1") (pin "2") (pinfunction "2_2") (pintype "passive"))
      (node (ref "T1") (pin "P") (pinfunction "P1_P") (pintype "passive"))
    )
    (net (code "23") (name "Net-(ESP-8266-URXD)") (class "Default")
      (node (ref "ESP-8266") (pin "4") (pinfunction "URXD_4") (pintype "passive"))
      (node (ref "J7") (pin "31") (pinfunction "WRX_31") (pintype "passive"))
    )
    (net (code "24") (name "Net-(ESP-8266-UTXD)") (class "Default")
      (node (ref "ESP-8266") (pin "5") (pinfunction "UTXD_5") (pintype "passive"))
      (node (ref "J7") (pin "32") (pinfunction "WTX_32") (pintype "passive"))
    )
    (net (code "25") (name "Net-(IN-1)") (class "Default")
      (node (ref "F1") (pin "1") (pinfunction "1_1") (pintype "passive"))
      (node (ref "IN") (pin "2") (pinfunction "1_2") (pintype "passive"))
      (node (ref "IN_2") (pin "1") (pinfunction "1_1") (pintype "passive"))
    )
    (net (code "26") (name "Net-(J2-CLK)") (class "Default")
      (node (ref "J2") (pin "5") (pinfunction "CLK_5") (pintype "passive"))
      (node (ref "R20") (pin "2") (pinfunction "2_2") (pintype "passive"))
      (node (ref "R23") (pin "1") (pinfunction "1_1") (pintype "passive"))
    )
    (net (code "27") (name "Net-(J2-CMD)") (class "Default")
      (node (ref "J2") (pin "2") (pinfunction "CMD_2") (pintype "passive"))
      (node (ref "R22") (pin "2") (pinfunction "2_2") (pintype "passive"))
      (node (ref "R25") (pin "1") (pinfunction "1_1") (pintype "passive"))
    )
    (net (code "28") (name "Net-(J2-VSS1)") (class "Default")
      (node (ref "J2") (pin "3") (pinfunction "VSS1_3") (pintype "passive"))
      (node (ref "R21") (pin "2") (pinfunction "2_2") (pintype "passive"))
      (node (ref "R24") (pin "1") (pinfunction "1_1") (pintype "passive"))
    )
    (net (code "29") (name "Net-(J7-CS)") (class "Default")
      (node (ref "J7") (pin "1") (pinfunction "CS_1") (pintype "passive"))
      (node (ref "LCD-MODULE") (pin "21") (pinfunction "LCD_CS_21") (pintype "passive"))
    )
    (net (code "30") (name "Net-(J7-DB0)") (class "Default")
      (node (ref "J7") (pin "6") (pinfunction "DB0_6") (pintype "passive"))
      (node (ref "LCD-MODULE") (pin "18") (pinfunction "DB0_18") (pintype "passive"))
    )
    (net (code "31") (name "Net-(J7-DB1)") (class "Default")
      (node (ref "J7") (pin "7") (pinfunction "DB1_7") (pintype "passive"))
      (node (ref "LCD-MODULE") (pin "17") (pinfunction "DB1_17") (pintype "passive"))
    )
    (net (code "32") (name "Net-(J7-DB2)") (class "Default")
      (node (ref "J7") (pin "8") (pinfunction "DB2_8") (pintype "passive"))
      (node (ref "LCD-MODULE") (pin "16") (pinfunction "DB2_16") (pintype "passive"))
    )
    (net (code "33") (name "Net-(J7-DB3)") (class "Default")
      (node (ref "J7") (pin "9") (pinfunction "DB3_9") (pintype "passive"))
      (node (ref "LCD-MODULE") (pin "15") (pinfunction "DB3_15") (pintype "passive"))
    )
    (net (code "34") (name "Net-(J7-DB4)") (class "Default")
      (node (ref "J7") (pin "10") (pinfunction "DB4_10") (pintype "passive"))
      (node (ref "LCD-MODULE") (pin "14") (pinfunction "DB4_14") (pintype "passive"))
    )
    (net (code "35") (name "Net-(J7-DB5)") (class "Default")
      (node (ref "J7") (pin "11") (pinfunction "DB5_11") (pintype "passive"))
      (node (ref "LCD-MODULE") (pin "13") (pinfunction "DB5_13") (pintype "passive"))
    )
    (net (code "36") (name "Net-(J7-DB6)") (class "Default")
      (node (ref "J7") (pin "12") (pinfunction "DB6_12") (pintype "passive"))
      (node (ref "LCD-MODULE") (pin "12") (pinfunction "DB6_12") (pintype "passive"))
    )
    (net (code "37") (name "Net-(J7-DB7)") (class "Default")
      (node (ref "J7") (pin "13") (pinfunction "DB7_13") (pintype "passive"))
      (node (ref "LCD-MODULE") (pin "11") (pinfunction "DB7_11") (pintype "passive"))
    )
    (net (code "38") (name "Net-(J7-DB8)") (class "Default")
      (node (ref "J7") (pin "14") (pinfunction "DB8_14") (pintype "passive"))
      (node (ref "LCD-MODULE") (pin "3") (pinfunction "DB8_3") (pintype "passive"))
    )
    (net (code "39") (name "Net-(J7-DB9)") (class "Default")
      (node (ref "J7") (pin "15") (pinfunction "DB9_15") (pintype "passive"))
      (node (ref "LCD-MODULE") (pin "4") (pinfunction "DB9_4") (pintype "passive"))
    )
    (net (code "40") (name "Net-(J7-DB10)") (class "Default")
      (node (ref "J7") (pin "16") (pinfunction "DB10_16") (pintype "passive"))
      (node (ref "LCD-MODULE") (pin "5") (pinfunction "DB10_5") (pintype "passive"))
    )
    (net (code "41") (name "Net-(J7-DB11)") (class "Default")
      (node (ref "J7") (pin "17") (pinfunction "DB11_17") (pintype "passive"))
      (node (ref "LCD-MODULE") (pin "6") (pinfunction "DB11_6") (pintype "passive"))
    )
    (net (code "42") (name "Net-(J7-DB12)") (class "Default")
      (node (ref "J7") (pin "18") (pinfunction "DB12_18") (pintype "passive"))
      (node (ref "LCD-MODULE") (pin "7") (pinfunction "DB12_7") (pintype "passive"))
    )
    (net (code "43") (name "Net-(J7-DB13)") (class "Default")
      (node (ref "J7") (pin "19") (pinfunction "DB13_19") (pintype "passive"))
      (node (ref "LCD-MODULE") (pin "8") (pinfunction "DB13_8") (pintype "passive"))
    )
    (net (code "44") (name "Net-(J7-DB14)") (class "Default")
      (node (ref "J7") (pin "20") (pinfunction "DB14_20") (pintype "passive"))
      (node (ref "LCD-MODULE") (pin "9") (pinfunction "DB14_9") (pintype "passive"))
    )
    (net (code "45") (name "Net-(J7-DB15)") (class "Default")
      (node (ref "J7") (pin "21") (pinfunction "DB15_21") (pintype "passive"))
      (node (ref "LCD-MODULE") (pin "10") (pinfunction "DB15_10") (pintype "passive"))
    )
    (net (code "46") (name "Net-(J7-RD)") (class "Default")
      (node (ref "J7") (pin "4") (pinfunction "RD_4") (pintype "passive"))
      (node (ref "LCD-MODULE") (pin "26") (pinfunction "LCD_RD_26") (pintype "passive"))
    )
    (net (code "47") (name "Net-(J7-RS)") (class "Default")
      (node (ref "J7") (pin "2") (pinfunction "RS_2") (pintype "passive"))
      (node (ref "LCD-MODULE") (pin "19") (pinfunction "LCD_RS_19") (pintype "passive"))
    )
    (net (code "48") (name "Net-(J7-RST)") (class "Default")
      (node (ref "J7") (pin "5") (pinfunction "RST_5") (pintype "passive"))
      (node (ref "LCD-MODULE") (pin "22") (pinfunction "LCD_RST_22") (pintype "passive"))
    )
    (net (code "49") (name "Net-(J7-WR)") (class "Default")
      (node (ref "J7") (pin "3") (pinfunction "WR_3") (pintype "passive"))
      (node (ref "LCD-MODULE") (pin "20") (pinfunction "LCD_WR_20") (pintype "passive"))
    )
    (net (code "50") (name "Net-(MOTHERBOARD-1)") (class "Default")
      (node (ref "F2") (pin "2") (pinfunction "2_2") (pintype "passive"))
      (node (ref "MOTHERBOARD") (pin "2") (pinfunction "1_2") (pintype "passive"))
    )
    (net (code "51") (name "Net-(R1-W)") (class "Default")
      (node (ref "R1") (pin "2") (pinfunction "W_2") (pintype "passive"))
      (node (ref "U2") (pin "7") (pinfunction "CH6_7") (pintype "passive"))
    )
    (net (code "52") (name "Net-(R2-W)") (class "Default")
      (node (ref "R2") (pin "2") (pinfunction "W_2") (pintype "passive"))
      (node (ref "U2") (pin "8") (pinfunction "CH7_8") (pintype "passive"))
    )
    (net (code "53") (name "Net-(U1-CH0)") (class "Default")
      (node (ref "R9") (pin "1") (pinfunction "1_1") (pintype "passive"))
      (node (ref "S8") (pin "1") (pinfunction "A_1") (pintype "passive"))
      (node (ref "S8") (pin "2") (pinfunction "A_2") (pintype "passive"))
      (node (ref "U1") (pin "1") (pinfunction "CH0_1") (pintype "passive"))
    )
    (net (code "54") (name "Net-(U1-CH1)") (class "Default")
      (node (ref "R10") (pin "1") (pinfunction "1_1") (pintype "passive"))
      (node (ref "S7") (pin "1") (pinfunction "A_1") (pintype "passive"))
      (node (ref "S7") (pin "2") (pinfunction "A_2") (pintype "passive"))
      (node (ref "U1") (pin "2") (pinfunction "CH1_2") (pintype "passive"))
    )
    (net (code "55") (name "Net-(U1-CH2)") (class "Default")
      (node (ref "R8") (pin "1") (pinfunction "1_1") (pintype "passive"))
      (node (ref "S6") (pin "1") (pinfunction "A_1") (pintype "passive"))
      (node (ref "S6") (pin "2") (pinfunction "A_2") (pintype "passive"))
      (node (ref "U1") (pin "3") (pinfunction "CH2_3") (pintype "passive"))
    )
    (net (code "56") (name "Net-(U1-CH3)") (class "Default")
      (node (ref "R7") (pin "1") (pinfunction "1_1") (pintype "passive"))
      (node (ref "S5") (pin "1") (pinfunction "A_1") (pintype "passive"))
      (node (ref "S5") (pin "2") (pinfunction "A_2") (pintype "passive"))
      (node (ref "U1") (pin "4") (pinfunction "CH3_4") (pintype "passive"))
    )
    (net (code "57") (name "Net-(U1-CH4)") (class "Default")
      (node (ref "R6") (pin "1") (pinfunction "1_1") (pintype "passive"))
      (node (ref "S4") (pin "1") (pinfunction "A_1") (pintype "passive"))
      (node (ref "S4") (pin "2") (pinfunction "A_2") (pintype "passive"))
      (node (ref "U1") (pin "5") (pinfunction "CH4_5") (pintype "passive"))
    )
    (net (code "58") (name "Net-(U1-CH5)") (class "Default")
      (node (ref "R5") (pin "1") (pinfunction "1_1") (pintype "passive"))
      (node (ref "S3") (pin "1") (pinfunction "A_1") (pintype "passive"))
      (node (ref "S3") (pin "2") (pinfunction "A_2") (pintype "passive"))
      (node (ref "U1") (pin "6") (pinfunction "CH5_6") (pintype "passive"))
    )
    (net (code "59") (name "Net-(U1-CH6)") (class "Default")
      (node (ref "R4") (pin "1") (pinfunction "1_1") (pintype "passive"))
      (node (ref "S2") (pin "1") (pinfunction "A_1") (pintype "passive"))
      (node (ref "S2") (pin "2") (pinfunction "A_2") (pintype "passive"))
      (node (ref "U1") (pin "7") (pinfunction "CH6_7") (pintype "passive"))
    )
    (net (code "60") (name "Net-(U1-CH7)") (class "Default")
      (node (ref "R3") (pin "1") (pinfunction "1_1") (pintype "passive"))
      (node (ref "S1") (pin "1") (pinfunction "A_1") (pintype "passive"))
      (node (ref "S1") (pin "2") (pinfunction "A_2") (pintype "passive"))
      (node (ref "U1") (pin "8") (pinfunction "CH7_8") (pintype "passive"))
    )
    (net (code "61") (name "Net-(U2-CH0)") (class "Default")
      (node (ref "R16") (pin "1") (pinfunction "1_1") (pintype "passive"))
      (node (ref "S14") (pin "1") (pinfunction "A_1") (pintype "passive"))
      (node (ref "S14") (pin "2") (pinfunction "A_2") (pintype "passive"))
      (node (ref "U2") (pin "1") (pinfunction "CH0_1") (pintype "passive"))
    )
    (net (code "62") (name "Net-(U2-CH1)") (class "Default")
      (node (ref "R15") (pin "1") (pinfunction "1_1") (pintype "passive"))
      (node (ref "S13") (pin "1") (pinfunction "A_1") (pintype "passive"))
      (node (ref "S13") (pin "2") (pinfunction "A_2") (pintype "passive"))
      (node (ref "U2") (pin "2") (pinfunction "CH1_2") (pintype "passive"))
    )
    (net (code "63") (name "Net-(U2-CH2)") (class "Default")
      (node (ref "R14") (pin "1") (pinfunction "1_1") (pintype "passive"))
      (node (ref "S12") (pin "1") (pinfunction "A_1") (pintype "passive"))
      (node (ref "S12") (pin "2") (pinfunction "A_2") (pintype "passive"))
      (node (ref "U2") (pin "3") (pinfunction "CH2_3") (pintype "passive"))
    )
    (net (code "64") (name "Net-(U2-CH3)") (class "Default")
      (node (ref "R13") (pin "1") (pinfunction "1_1") (pintype "passive"))
      (node (ref "S11") (pin "1") (pinfunction "A_1") (pintype "passive"))
      (node (ref "S11") (pin "2") (pinfunction "A_2") (pintype "passive"))
      (node (ref "U2") (pin "4") (pinfunction "CH3_4") (pintype "passive"))
    )
    (net (code "65") (name "Net-(U2-CH4)") (class "Default")
      (node (ref "R12") (pin "1") (pinfunction "1_1") (pintype "passive"))
      (node (ref "S10") (pin "1") (pinfunction "A_1") (pintype "passive"))
      (node (ref "S10") (pin "2") (pinfunction "A_2") (pintype "passive"))
      (node (ref "U2") (pin "5") (pinfunction "CH4_5") (pintype "passive"))
    )
    (net (code "66") (name "Net-(U2-CH5)") (class "Default")
      (node (ref "R11") (pin "1") (pinfunction "1_1") (pintype "passive"))
      (node (ref "S9") (pin "1") (pinfunction "A_1") (pintype "passive"))
      (node (ref "S9") (pin "2") (pinfunction "A_2") (pintype "passive"))
      (node (ref "U2") (pin "6") (pinfunction "CH5_6") (pintype "passive"))
    )
    (net (code "67") (name "Net-(U3-CH0)") (class "Default")
      (node (ref "R29") (pin "1") (pinfunction "1_1") (pintype "passive"))
      (node (ref "S23") (pin "1") (pinfunction "A_1") (pintype "passive"))
      (node (ref "S23") (pin "2") (pinfunction "A_2") (pintype "passive"))
      (node (ref "U3") (pin "1") (pinfunction "CH0_1") (pintype "passive"))
    )
    (net (code "68") (name "Net-(U3-CH1)") (class "Default")
      (node (ref "R30") (pin "1") (pinfunction "1_1") (pintype "passive"))
      (node (ref "S22") (pin "1") (pinfunction "A_1") (pintype "passive"))
      (node (ref "S22") (pin "2") (pinfunction "A_2") (pintype "passive"))
      (node (ref "U3") (pin "2") (pinfunction "CH1_2") (pintype "passive"))
    )
    (net (code "69") (name "Net-(U3-CH2)") (class "Default")
      (node (ref "R31") (pin "1") (pinfunction "1_1") (pintype "passive"))
      (node (ref "S21") (pin "1") (pinfunction "A_1") (pintype "passive"))
      (node (ref "S21") (pin "2") (pinfunction "A_2") (pintype "passive"))
      (node (ref "U3") (pin "3") (pinfunction "CH2_3") (pintype "passive"))
    )
    (net (code "70") (name "Net-(U3-CH3)") (class "Default")
      (node (ref "R32") (pin "1") (pinfunction "1_1") (pintype "passive"))
      (node (ref "S20") (pin "1") (pinfunction "A_1") (pintype "passive"))
      (node (ref "S20") (pin "2") (pinfunction "A_2") (pintype "passive"))
      (node (ref "U3") (pin "4") (pinfunction "CH3_4") (pintype "passive"))
    )
    (net (code "71") (name "Net-(U3-CH4)") (class "Default")
      (node (ref "R33") (pin "1") (pinfunction "1_1") (pintype "passive"))
      (node (ref "S19") (pin "1") (pinfunction "A_1") (pintype "passive"))
      (node (ref "S19") (pin "2") (pinfunction "A_2") (pintype "passive"))
      (node (ref "U3") (pin "5") (pinfunction "CH4_5") (pintype "passive"))
    )
    (net (code "72") (name "Net-(U3-CH5)") (class "Default")
      (node (ref "R34") (pin "1") (pinfunction "1_1") (pintype "passive"))
      (node (ref "S18") (pin "1") (pinfunction "A_1") (pintype "passive"))
      (node (ref "S18") (pin "2") (pinfunction "A_2") (pintype "passive"))
      (node (ref "U3") (pin "6") (pinfunction "CH5_6") (pintype "passive"))
    )
    (net (code "73") (name "Net-(U3-CH6)") (class "Default")
      (node (ref "R35") (pin "1") (pinfunction "1_1") (pintype "passive"))
      (node (ref "S17") (pin "1") (pinfunction "A_1") (pintype "passive"))
      (node (ref "S17") (pin "2") (pinfunction "A_2") (pintype "passive"))
      (node (ref "U3") (pin "7") (pinfunction "CH6_7") (pintype "passive"))
    )
    (net (code "74") (name "Net-(U3-CH7)") (class "Default")
      (node (ref "R36") (pin "1") (pinfunction "1_1") (pintype "passive"))
      (node (ref "S16") (pin "1") (pinfunction "A_1") (pintype "passive"))
      (node (ref "S16") (pin "2") (pinfunction "A_2") (pintype "passive"))
      (node (ref "U3") (pin "8") (pinfunction "CH7_8") (pintype "passive"))
    )
    (net (code "75") (name "VCC12_IN") (class "Default")
      (node (ref "ACCUM") (pin "2") (pinfunction "1_2") (pintype "passive"))
      (node (ref "Q1") (pin "3") (pinfunction "S_3") (pintype "passive"))
      (node (ref "R26") (pin "2") (pinfunction "2_2") (pintype "passive"))
      (node (ref "R27") (pin "2") (pinfunction "2_2") (pintype "passive"))
      (node (ref "T1") (pin "LCP") (pinfunction "P2_LCP") (pintype "passive"))
    )
    (net (code "76") (name "unconnected-(ESP-8266-GPIO0-Pad3)") (class "Default")
      (node (ref "ESP-8266") (pin "3") (pinfunction "GPIO0_3") (pintype "passive"))
    )
    (net (code "77") (name "unconnected-(ESP-8266-GPIO2-Pad2)") (class "Default")
      (node (ref "ESP-8266") (pin "2") (pinfunction "GPIO2_2") (pintype "passive"))
    )
    (net (code "78") (name "unconnected-(ESP-8266-GPIO16-Pad7)") (class "Default")
      (node (ref "ESP-8266") (pin "7") (pinfunction "GPIO16_7") (pintype "passive"))
    )
    (net (code "79") (name "unconnected-(J2-CD{slash}DAT3-Pad1)") (class "Default")
      (node (ref "J2") (pin "1") (pinfunction "CD/DAT3_1") (pintype "passive"))
    )
    (net (code "80") (name "unconnected-(J2-DAT1-Pad8)") (class "Default")
      (node (ref "J2") (pin "8") (pinfunction "DAT1_8") (pintype "passive"))
    )
    (net (code "81") (name "unconnected-(LCD-MODULE-NC-Pad23)") (class "Default")
      (node (ref "LCD-MODULE") (pin "23") (pinfunction "NC_23") (pintype "passive"))
    )
    (net (code "82") (name "unconnected-(LCD-MODULE-NC-Pad24)") (class "Default")
      (node (ref "LCD-MODULE") (pin "24") (pinfunction "NC_24") (pintype "passive"))
    )
    (net (code "83") (name "unconnected-(LCD-MODULE-NC-Pad25)") (class "Default")
      (node (ref "LCD-MODULE") (pin "25") (pinfunction "NC_25") (pintype "passive"))
    )
    (net (code "84") (name "unconnected-(LCD-MODULE-NC-Pad27)") (class "Default")
      (node (ref "LCD-MODULE") (pin "27") (pinfunction "NC_27") (pintype "passive"))
    )
    (net (code "85") (name "unconnected-(LCD-MODULE-NC-Pad28)") (class "Default")
      (node (ref "LCD-MODULE") (pin "28") (pinfunction "NC_28") (pintype "passive"))
    )
    (net (code "86") (name "unconnected-(LCD-MODULE-NC-Pad29)") (class "Default")
      (node (ref "LCD-MODULE") (pin "29") (pinfunction "NC_29") (pintype "passive"))
    )
    (net (code "87") (name "unconnected-(LCD-MODULE-NC-Pad30)") (class "Default")
      (node (ref "LCD-MODULE") (pin "30") (pinfunction "NC_30") (pintype "passive"))
    )
    (net (code "88") (name "unconnected-(LCD-MODULE-RESET-Pad37)") (class "Default")
      (node (ref "LCD-MODULE") (pin "37") (pinfunction "RESET_37") (pintype "passive"))
    )
    (net (code "89") (name "unconnected-(LCD-MODULE-SD_CLK-Pad33)") (class "Default")
      (node (ref "LCD-MODULE") (pin "33") (pinfunction "SD_CLK_33") (pintype "passive"))
    )
    (net (code "90") (name "unconnected-(LCD-MODULE-SD_CS-Pad34)") (class "Default")
      (node (ref "LCD-MODULE") (pin "34") (pinfunction "SD_CS_34") (pintype "passive"))
    )
    (net (code "91") (name "unconnected-(LCD-MODULE-SD_MISO-Pad31)") (class "Default")
      (node (ref "LCD-MODULE") (pin "31") (pinfunction "SD_MISO_31") (pintype "passive"))
    )
    (net (code "92") (name "unconnected-(LCD-MODULE-SD_MOSI-Pad32)") (class "Default")
      (node (ref "LCD-MODULE") (pin "32") (pinfunction "SD_MOSI_32") (pintype "passive"))
    )
  )
)
